# SparkFun_RTK_Facet_-_Cellular.net
KiCad netlist of a schematic drawn in EAGLE
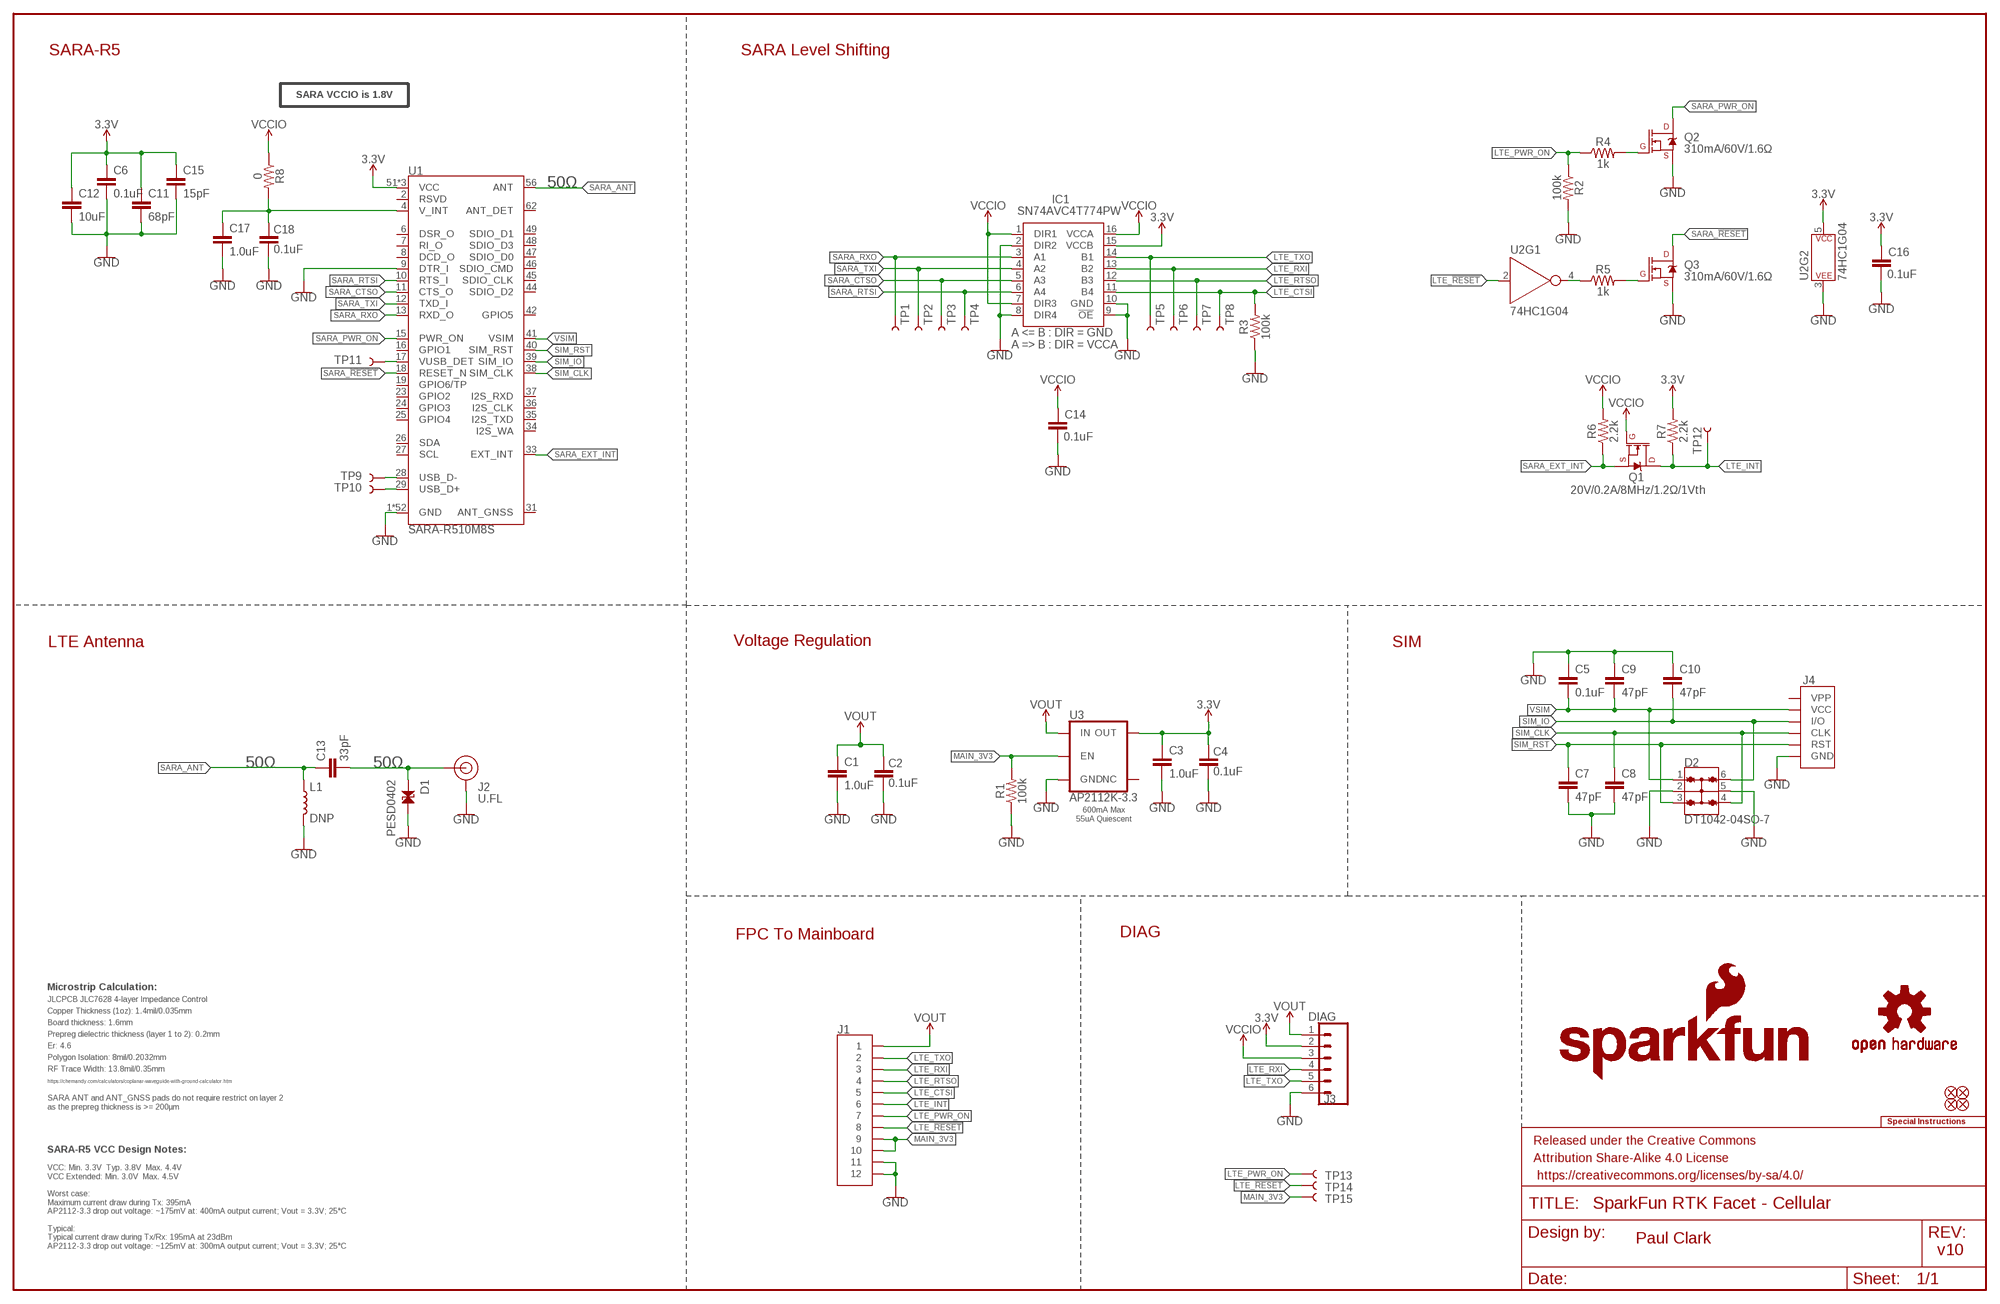
[diagram p0: schematic, sheet 1]

(export (version "E")
  (design (tool "Eeschema 10.0.6"))
  (components
    (comp (ref "C1")
      (value "1.0uF")
      (footprint "eagle-import:0603")
      (libsource (lib "eagle-import") (part "1.0UF-0603-16V-10%-X7R"))
    )
    (comp (ref "C2")
      (value "0.1uF")
      (footprint "eagle-import:0603")
      (libsource (lib "eagle-import") (part "0.1UF-0603-25V-5%"))
    )
    (comp (ref "C3")
      (value "1.0uF")
      (footprint "eagle-import:0603")
      (libsource (lib "eagle-import") (part "1.0UF-0603-16V-10%-X7R"))
    )
    (comp (ref "C4")
      (value "0.1uF")
      (footprint "eagle-import:0603")
      (libsource (lib "eagle-import") (part "0.1UF-0603-25V-5%"))
    )
    (comp (ref "C5")
      (value "0.1uF")
      (footprint "eagle-import:0603")
      (libsource (lib "eagle-import") (part "0.1UF-0603-25V-5%"))
    )
    (comp (ref "C6")
      (value "0.1uF")
      (footprint "eagle-import:0603")
      (libsource (lib "eagle-import") (part "0.1UF-0603-25V-5%"))
    )
    (comp (ref "C7")
      (value "47pF")
      (footprint "eagle-import:0603")
      (libsource (lib "eagle-import") (part "47PF-0603-50V-5%"))
    )
    (comp (ref "C8")
      (value "47pF")
      (footprint "eagle-import:0603")
      (libsource (lib "eagle-import") (part "47PF-0603-50V-5%"))
    )
    (comp (ref "C9")
      (value "47pF")
      (footprint "eagle-import:0603")
      (libsource (lib "eagle-import") (part "47PF-0603-50V-5%"))
    )
    (comp (ref "C10")
      (value "47pF")
      (footprint "eagle-import:0603")
      (libsource (lib "eagle-import") (part "47PF-0603-50V-5%"))
    )
    (comp (ref "C11")
      (value "68pF")
      (footprint "eagle-import:0603")
      (libsource (lib "eagle-import") (part "68PF-0603-50V-5%"))
    )
    (comp (ref "C12")
      (value "10uF")
      (footprint "eagle-import:0603")
      (libsource (lib "eagle-import") (part "10UF-0603-6.3V-20%"))
    )
    (comp (ref "C13")
      (value "33pF")
      (footprint "eagle-import:0402")
      (fields
        (field (name "DIGIKEY_PART") "490-5936-1-ND")
        (field (name "MANUFACTURER") "Murata")
        (field (name "MANU_PART") "GRM1555C1H330JA")
      )
      (libsource (lib "eagle-import") (part "33PF-0402-25V-5%-X7R"))
    )
    (comp (ref "C14")
      (value "0.1uF")
      (footprint "eagle-import:0603")
      (libsource (lib "eagle-import") (part "0.1UF-0603-25V-(+80/-20%)"))
    )
    (comp (ref "C15")
      (value "15pF")
      (footprint "eagle-import:0603")
      (libsource (lib "eagle-import") (part "15PF-0603-50V-5%"))
    )
    (comp (ref "C16")
      (value "0.1uF")
      (footprint "eagle-import:0603")
      (libsource (lib "eagle-import") (part "0.1UF-0603-25V-(+80/-20%)"))
    )
    (comp (ref "C17")
      (value "1.0uF")
      (footprint "eagle-import:0603")
      (libsource (lib "eagle-import") (part "1.0UF-0603-16V-10%-X7R"))
    )
    (comp (ref "C18")
      (value "0.1uF")
      (footprint "eagle-import:0603")
      (libsource (lib "eagle-import") (part "0.1UF-0603-25V-5%"))
    )
    (comp (ref "D1")
      (value "PESD0402")
      (footprint "eagle-import:0402")
      (fields
        (field (name "DIGIKEY_PART") "PESD0402-140CT-ND")
        (field (name "MOUSE_PART") "650-PESD0402-140")
      )
      (libsource (lib "eagle-import") (part "PESD0402"))
    )
    (comp (ref "D2")
      (value "DT1042-04SO-7")
      (footprint "eagle-import:SOT23-6L")
      (libsource (lib "eagle-import") (part "TVS_DIODE_ARRAY_4DT1042-04SO-7"))
    )
    (comp (ref "FID1")
      (value "FIDUCIAL1X2")
      (footprint "eagle-import:FIDUCIAL-1X2")
      (libsource (lib "eagle-import") (part "FIDUCIAL1X2"))
    )
    (comp (ref "FID2")
      (value "FIDUCIAL1X2")
      (footprint "eagle-import:FIDUCIAL-1X2")
      (libsource (lib "eagle-import") (part "FIDUCIAL1X2"))
    )
    (comp (ref "FID3")
      (value "FIDUCIAL1X2")
      (footprint "eagle-import:FIDUCIAL-1X2")
      (libsource (lib "eagle-import") (part "FIDUCIAL1X2"))
    )
    (comp (ref "FID4")
      (value "FIDUCIAL1X2")
      (footprint "eagle-import:FIDUCIAL-1X2")
      (libsource (lib "eagle-import") (part "FIDUCIAL1X2"))
    )
    (comp (ref "FRAME3")
      (value "FRAME-LEDGER")
      (footprint "eagle-import:CREATIVE_COMMONS")
      (libsource (lib "eagle-import") (part "FRAME-LEDGER"))
    )
    (comp (ref "IC1")
      (value "SN74AVC4T774PW")
      (footprint "eagle-import:SOP65P640X120-16N")
      (fields (field (name "MOUSER_PART_NUMBER") "595-SN74AVC4T774PW"))
      (libsource (lib "eagle-import") (part "SN74AVC4T774PW"))
    )
    (comp (ref "J1")
      (value "FPC_12_0.5MM_BACKFLIP")
      (footprint "eagle-import:FPC_12_DOUBLESIDED_BACKFLIP")
      (libsource (lib "eagle-import") (part "FPC_12_0.5MM_BACKFLIP"))
    )
    (comp (ref "J2")
      (value "U.FL")
      (footprint "eagle-import:U.FL")
      (libsource (lib "eagle-import") (part "U.FL2PIN"))
    )
    (comp (ref "J3")
      (value "DIAG")
      (footprint "eagle-import:1X06_NO_SILK")
      (libsource (lib "eagle-import") (part "CONN_06NO_SILK_FEMALE_PTH"))
    )
    (comp (ref "J4")
      (value "SIMHOLDER-PUSHPUSH-REDUCED-PADS")
      (footprint "eagle-import:NANO_SIM_PP_REDUCED_PADS")
      (libsource (lib "eagle-import") (part "SIMHOLDER-PUSHPUSH-REDUCED-PADS"))
    )
    (comp (ref "L1")
      (value "DNP")
      (footprint "eagle-import:0402_COILCRAFT")
      (libsource (lib "eagle-import") (part "INDUCTOR_DNP-0402"))
    )
    (comp (ref "LOGO1")
      (value "SPECIAL_INSTRUCTIONS-ORDERING")
      (footprint "eagle-import:ORDERING_INSTRUCTIONS")
      (libsource (lib "eagle-import") (part "SPECIAL_INSTRUCTIONS-ORDERING"))
    )
    (comp (ref "LOGO2")
      (value "SFE_LOGO_NAME_FLAME.1_INCH")
      (footprint "eagle-import:SFE_LOGO_NAME_FLAME_.1")
      (libsource (lib "eagle-import") (part "SFE_LOGO_NAME_FLAME.1_INCH"))
    )
    (comp (ref "LOGO3")
      (value "OSHW-LOGOMINI")
      (footprint "eagle-import:OSHW-LOGO-MINI")
      (libsource (lib "eagle-import") (part "OSHW-LOGOMINI"))
    )
    (comp (ref "LOGO4")
      (value "OSHW-LOGOMINI")
      (footprint "eagle-import:OSHW-LOGO-MINI")
      (libsource (lib "eagle-import") (part "OSHW-LOGOMINI"))
    )
    (comp (ref "LOGO5")
      (value "SFE_LOGO_NAME_FLAME.1_INCH")
      (footprint "eagle-import:SFE_LOGO_NAME_FLAME_.1")
      (libsource (lib "eagle-import") (part "SFE_LOGO_NAME_FLAME.1_INCH"))
    )
    (comp (ref "Q1")
      (value "20V/0.2A/8MHz/1.2Ω/1Vth")
      (footprint "eagle-import:SOT-416FL")
      (libsource (lib "eagle-import") (part "MOSFET-NCH-RE1C002UNTCL"))
    )
    (comp (ref "Q2")
      (value "310mA/60V/1.6Ω")
      (footprint "eagle-import:SOT323")
      (libsource (lib "eagle-import") (part "MOSFET-NCH-2N7002PW"))
    )
    (comp (ref "Q3")
      (value "310mA/60V/1.6Ω")
      (footprint "eagle-import:SOT323")
      (libsource (lib "eagle-import") (part "MOSFET-NCH-2N7002PW"))
    )
    (comp (ref "R1")
      (value "100k")
      (footprint "eagle-import:0603")
      (libsource (lib "eagle-import") (part "100KOHM-0603-1/10W-1%"))
    )
    (comp (ref "R2")
      (value "100k")
      (footprint "eagle-import:0603")
      (libsource (lib "eagle-import") (part "100KOHM-0603-1/10W-1%"))
    )
    (comp (ref "R3")
      (value "100k")
      (footprint "eagle-import:0603")
      (libsource (lib "eagle-import") (part "100KOHM-0603-1/10W-1%"))
    )
    (comp (ref "R4")
      (value "1k")
      (footprint "eagle-import:0603")
      (libsource (lib "eagle-import") (part "1KOHM-0603-1/10W-1%"))
    )
    (comp (ref "R5")
      (value "1k")
      (footprint "eagle-import:0603")
      (libsource (lib "eagle-import") (part "1KOHM-0603-1/10W-1%"))
    )
    (comp (ref "R6")
      (value "2.2k")
      (footprint "eagle-import:0603")
      (libsource (lib "eagle-import") (part "2.2KOHM-0603-1/10W-1%"))
    )
    (comp (ref "R7")
      (value "2.2k")
      (footprint "eagle-import:0603")
      (libsource (lib "eagle-import") (part "2.2KOHM-0603-1/10W-1%"))
    )
    (comp (ref "R8")
      (value "0")
      (footprint "eagle-import:0603")
      (libsource (lib "eagle-import") (part "0OHM-0603-1/10W"))
    )
    (comp (ref "TP1")
      (value "TEST-POINT3")
      (footprint "eagle-import:PAD.03X.03")
      (libsource (lib "eagle-import") (part "TEST-POINT3"))
    )
    (comp (ref "TP2")
      (value "TEST-POINT3")
      (footprint "eagle-import:PAD.03X.03")
      (libsource (lib "eagle-import") (part "TEST-POINT3"))
    )
    (comp (ref "TP3")
      (value "TEST-POINT3")
      (footprint "eagle-import:PAD.03X.03")
      (libsource (lib "eagle-import") (part "TEST-POINT3"))
    )
    (comp (ref "TP4")
      (value "TEST-POINT3")
      (footprint "eagle-import:PAD.03X.03")
      (libsource (lib "eagle-import") (part "TEST-POINT3"))
    )
    (comp (ref "TP5")
      (value "TEST-POINT3")
      (footprint "eagle-import:PAD.03X.03")
      (libsource (lib "eagle-import") (part "TEST-POINT3"))
    )
    (comp (ref "TP6")
      (value "TEST-POINT3")
      (footprint "eagle-import:PAD.03X.03")
      (libsource (lib "eagle-import") (part "TEST-POINT3"))
    )
    (comp (ref "TP7")
      (value "TEST-POINT3")
      (footprint "eagle-import:PAD.03X.03")
      (libsource (lib "eagle-import") (part "TEST-POINT3"))
    )
    (comp (ref "TP8")
      (value "TEST-POINT3")
      (footprint "eagle-import:PAD.03X.03")
      (libsource (lib "eagle-import") (part "TEST-POINT3"))
    )
    (comp (ref "TP9")
      (value "TEST-POINT3")
      (footprint "eagle-import:PAD.03X.03")
      (libsource (lib "eagle-import") (part "TEST-POINT3"))
    )
    (comp (ref "TP10")
      (value "TEST-POINT3")
      (footprint "eagle-import:PAD.03X.03")
      (libsource (lib "eagle-import") (part "TEST-POINT3"))
    )
    (comp (ref "TP11")
      (value "TEST-POINT3")
      (footprint "eagle-import:PAD.03X.03")
      (libsource (lib "eagle-import") (part "TEST-POINT3"))
    )
    (comp (ref "TP12")
      (value "TEST-POINT3")
      (footprint "eagle-import:PAD.03X.03")
      (libsource (lib "eagle-import") (part "TEST-POINT3"))
    )
    (comp (ref "TP13")
      (value "TEST-POINT3")
      (footprint "eagle-import:PAD.03X.03")
      (libsource (lib "eagle-import") (part "TEST-POINT3"))
    )
    (comp (ref "TP14")
      (value "TEST-POINT3")
      (footprint "eagle-import:PAD.03X.03")
      (libsource (lib "eagle-import") (part "TEST-POINT3"))
    )
    (comp (ref "TP15")
      (value "TEST-POINT3")
      (footprint "eagle-import:PAD.03X.03")
      (libsource (lib "eagle-import") (part "TEST-POINT3"))
    )
    (comp (ref "U1")
      (value "SARA-R510M8S")
      (footprint "eagle-import:SARA-LGA")
      (libsource (lib "eagle-import") (part "SARA-R510M8S"))
    )
    (comp (ref "U2")
      (value "74HC1G04")
      (footprint "eagle-import:SOT353")
      (libsource (lib "eagle-import") (part "741G04HC"))
    )
    (comp (ref "U3")
      (value "AP2112K-3.3")
      (footprint "eagle-import:SOT23-5")
      (libsource (lib "eagle-import") (part "V_REG_AP2112K-3.3V"))
    )
  )
  (nets
    (net (code "1") (name "/LTE_~{RESET}") (class "Default")
      (node (ref "J1") (pin "8") (pinfunction "8_8") (pintype "bidirectional"))
      (node (ref "TP14") (pin "1") (pinfunction "1_1") (pintype "bidirectional"))
      (node (ref "U2") (pin "2") (pinfunction "A_2") (pintype "bidirectional"))
    )
    (net (code "2") (name "/SARA_~{RESET}") (class "Default")
      (node (ref "Q3") (pin "3") (pinfunction "D_3") (pintype "bidirectional"))
      (node (ref "U1") (pin "18") (pinfunction "RESET_N_18") (pintype "input"))
    )
    (net (code "3") (name "3.3V") (class "Default")
      (node (ref "C11") (pin "1") (pinfunction "1_1") (pintype "passive"))
      (node (ref "C12") (pin "1") (pinfunction "1_1") (pintype "passive"))
      (node (ref "C15") (pin "1") (pinfunction "1_1") (pintype "passive"))
      (node (ref "C16") (pin "1") (pinfunction "1_1") (pintype "passive"))
      (node (ref "C3") (pin "1") (pinfunction "1_1") (pintype "passive"))
      (node (ref "C4") (pin "2") (pinfunction "2_2") (pintype "passive"))
      (node (ref "C6") (pin "1") (pinfunction "1_1") (pintype "passive"))
      (node (ref "IC1") (pin "15") (pinfunction "VCCB_15") (pintype "power_in"))
      (node (ref "J3") (pin "2") (pinfunction "2_2") (pintype "passive"))
      (node (ref "R7") (pin "2") (pinfunction "2_2") (pintype "passive"))
      (node (ref "U1") (pin "51") (pinfunction "VCC_51") (pintype "power_in"))
      (node (ref "U1") (pin "52") (pinfunction "VCC_52") (pintype "power_in"))
      (node (ref "U1") (pin "53") (pinfunction "VCC_53") (pintype "power_in"))
      (node (ref "U2") (pin "5") (pinfunction "P$V+_5") (pintype "bidirectional"))
      (node (ref "U3") (pin "5") (pinfunction "OUT_5") (pintype "passive"))
    )
    (net (code "4") (name "GND") (class "Default")
      (node (ref "C1") (pin "2") (pinfunction "2_2") (pintype "passive"))
      (node (ref "C10") (pin "1") (pinfunction "1_1") (pintype "passive"))
      (node (ref "C11") (pin "2") (pinfunction "2_2") (pintype "passive"))
      (node (ref "C12") (pin "2") (pinfunction "2_2") (pintype "passive"))
      (node (ref "C14") (pin "2") (pinfunction "2_2") (pintype "passive"))
      (node (ref "C15") (pin "2") (pinfunction "2_2") (pintype "passive"))
      (node (ref "C16") (pin "2") (pinfunction "2_2") (pintype "passive"))
      (node (ref "C17") (pin "2") (pinfunction "2_2") (pintype "passive"))
      (node (ref "C18") (pin "1") (pinfunction "1_1") (pintype "passive"))
      (node (ref "C2") (pin "1") (pinfunction "1_1") (pintype "passive"))
      (node (ref "C3") (pin "2") (pinfunction "2_2") (pintype "passive"))
      (node (ref "C4") (pin "1") (pinfunction "1_1") (pintype "passive"))
      (node (ref "C5") (pin "1") (pinfunction "1_1") (pintype "passive"))
      (node (ref "C6") (pin "2") (pinfunction "2_2") (pintype "passive"))
      (node (ref "C7") (pin "2") (pinfunction "2_2") (pintype "passive"))
      (node (ref "C8") (pin "2") (pinfunction "2_2") (pintype "passive"))
      (node (ref "C9") (pin "1") (pinfunction "1_1") (pintype "passive"))
      (node (ref "D1") (pin "2") (pinfunction "2_2") (pintype "bidirectional"))
      (node (ref "D2") (pin "2") (pinfunction "2_2") (pintype "bidirectional"))
      (node (ref "D2") (pin "5") (pinfunction "5_5") (pintype "bidirectional"))
      (node (ref "IC1") (pin "10") (pinfunction "GND_10") (pintype "power_in"))
      (node (ref "IC1") (pin "2") (pinfunction "DIR2_2") (pintype "input"))
      (node (ref "IC1") (pin "8") (pinfunction "DIR4_8") (pintype "input"))
      (node (ref "IC1") (pin "9") (pinfunction "~{OE}_9") (pintype "input"))
      (node (ref "J1") (pin "11") (pinfunction "11_11") (pintype "bidirectional"))
      (node (ref "J1") (pin "12") (pinfunction "12_12") (pintype "bidirectional"))
      (node (ref "J2") (pin "1") (pinfunction "GND_1") (pintype "bidirectional"))
      (node (ref "J2") (pin "2") (pinfunction "GND_2") (pintype "bidirectional"))
      (node (ref "J3") (pin "6") (pinfunction "6_6") (pintype "passive"))
      (node (ref "J4") (pin "C5") (pinfunction "GND_C5") (pintype "power_in"))
      (node (ref "L1") (pin "P$2") (pinfunction "2_P$2") (pintype "passive"))
      (node (ref "Q2") (pin "2") (pinfunction "S_2") (pintype "bidirectional"))
      (node (ref "Q3") (pin "2") (pinfunction "S_2") (pintype "bidirectional"))
      (node (ref "R1") (pin "1") (pinfunction "1_1") (pintype "passive"))
      (node (ref "R2") (pin "2") (pinfunction "2_2") (pintype "passive"))
      (node (ref "R3") (pin "1") (pinfunction "1_1") (pintype "passive"))
      (node (ref "U1") (pin "1") (pinfunction "GND_1") (pintype "power_in"))
      (node (ref "U1") (pin "14") (pinfunction "GND_14") (pintype "power_in"))
      (node (ref "U1") (pin "20") (pinfunction "GND_20") (pintype "power_in"))
      (node (ref "U1") (pin "21") (pinfunction "GND_21") (pintype "power_in"))
      (node (ref "U1") (pin "22") (pinfunction "GND_22") (pintype "power_in"))
      (node (ref "U1") (pin "3") (pinfunction "GND_3") (pintype "power_in"))
      (node (ref "U1") (pin "30") (pinfunction "GND_30") (pintype "power_in"))
      (node (ref "U1") (pin "32") (pinfunction "GND_32") (pintype "power_in"))
      (node (ref "U1") (pin "43") (pinfunction "GND_43") (pintype "power_in"))
      (node (ref "U1") (pin "5") (pinfunction "GND_5") (pintype "power_in"))
      (node (ref "U1") (pin "50") (pinfunction "GND_50") (pintype "power_in"))
      (node (ref "U1") (pin "54") (pinfunction "GND_54") (pintype "power_in"))
      (node (ref "U1") (pin "55") (pinfunction "GND_55") (pintype "power_in"))
      (node (ref "U1") (pin "57") (pinfunction "GND_57") (pintype "power_in"))
      (node (ref "U1") (pin "58") (pinfunction "GND_58") (pintype "power_in"))
      (node (ref "U1") (pin "59") (pinfunction "GND_59") (pintype "power_in"))
      (node (ref "U1") (pin "60") (pinfunction "GND_60") (pintype "power_in"))
      (node (ref "U1") (pin "61") (pinfunction "GND_61") (pintype "power_in"))
      (node (ref "U1") (pin "63") (pinfunction "GND_63") (pintype "power_in"))
      (node (ref "U1") (pin "64") (pinfunction "GND_64") (pintype "power_in"))
      (node (ref "U1") (pin "65") (pinfunction "GND_65") (pintype "power_in"))
      (node (ref "U1") (pin "66") (pinfunction "GND_66") (pintype "power_in"))
      (node (ref "U1") (pin "67") (pinfunction "GND_67") (pintype "power_in"))
      (node (ref "U1") (pin "68") (pinfunction "GND_68") (pintype "power_in"))
      (node (ref "U1") (pin "69") (pinfunction "GND_69") (pintype "power_in"))
      (node (ref "U1") (pin "70") (pinfunction "GND_70") (pintype "power_in"))
      (node (ref "U1") (pin "71") (pinfunction "GND_71") (pintype "power_in"))
      (node (ref "U1") (pin "72") (pinfunction "GND_72") (pintype "power_in"))
      (node (ref "U1") (pin "73") (pinfunction "GND_73") (pintype "power_in"))
      (node (ref "U1") (pin "74") (pinfunction "GND_74") (pintype "power_in"))
      (node (ref "U1") (pin "75") (pinfunction "GND_75") (pintype "power_in"))
      (node (ref "U1") (pin "76") (pinfunction "GND_76") (pintype "power_in"))
      (node (ref "U1") (pin "77") (pinfunction "GND_77") (pintype "power_in"))
      (node (ref "U1") (pin "78") (pinfunction "GND_78") (pintype "power_in"))
      (node (ref "U1") (pin "79") (pinfunction "GND_79") (pintype "power_in"))
      (node (ref "U1") (pin "80") (pinfunction "GND_80") (pintype "power_in"))
      (node (ref "U1") (pin "81") (pinfunction "GND_81") (pintype "power_in"))
      (node (ref "U1") (pin "82") (pinfunction "GND_82") (pintype "power_in"))
      (node (ref "U1") (pin "83") (pinfunction "GND_83") (pintype "power_in"))
      (node (ref "U1") (pin "84") (pinfunction "GND_84") (pintype "power_in"))
      (node (ref "U1") (pin "85") (pinfunction "GND_85") (pintype "power_in"))
      (node (ref "U1") (pin "86") (pinfunction "GND_86") (pintype "power_in"))
      (node (ref "U1") (pin "87") (pinfunction "GND_87") (pintype "power_in"))
      (node (ref "U1") (pin "88") (pinfunction "GND_88") (pintype "power_in"))
      (node (ref "U1") (pin "89") (pinfunction "GND_89") (pintype "power_in"))
      (node (ref "U1") (pin "9") (pinfunction "DTR_I_9") (pintype "input"))
      (node (ref "U1") (pin "90") (pinfunction "GND_90") (pintype "power_in"))
      (node (ref "U1") (pin "91") (pinfunction "GND_91") (pintype "power_in"))
      (node (ref "U1") (pin "92") (pinfunction "GND_92") (pintype "power_in"))
      (node (ref "U1") (pin "93") (pinfunction "GND_93") (pintype "power_in"))
      (node (ref "U1") (pin "94") (pinfunction "GND_94") (pintype "power_in"))
      (node (ref "U1") (pin "95") (pinfunction "GND_95") (pintype "power_in"))
      (node (ref "U1") (pin "96") (pinfunction "GND_96") (pintype "power_in"))
      (node (ref "U2") (pin "3") (pinfunction "P$V-_3") (pintype "bidirectional"))
      (node (ref "U3") (pin "2") (pinfunction "GND_2") (pintype "input"))
    )
    (net (code "5") (name "LTE_CTSI") (class "Default")
      (node (ref "IC1") (pin "11") (pinfunction "B4_11") (pintype "bidirectional"))
      (node (ref "J1") (pin "5") (pinfunction "5_5") (pintype "bidirectional"))
      (node (ref "R3") (pin "2") (pinfunction "2_2") (pintype "passive"))
      (node (ref "TP8") (pin "1") (pinfunction "1_1") (pintype "bidirectional"))
    )
    (net (code "6") (name "LTE_INT") (class "Default")
      (node (ref "J1") (pin "6") (pinfunction "6_6") (pintype "bidirectional"))
      (node (ref "Q1") (pin "3") (pinfunction "D_3") (pintype "bidirectional"))
      (node (ref "R7") (pin "1") (pinfunction "1_1") (pintype "passive"))
      (node (ref "TP12") (pin "1") (pinfunction "1_1") (pintype "bidirectional"))
    )
    (net (code "7") (name "LTE_PWR_ON") (class "Default")
      (node (ref "J1") (pin "7") (pinfunction "7_7") (pintype "bidirectional"))
      (node (ref "R2") (pin "1") (pinfunction "1_1") (pintype "passive"))
      (node (ref "R4") (pin "1") (pinfunction "1_1") (pintype "passive"))
      (node (ref "TP13") (pin "1") (pinfunction "1_1") (pintype "bidirectional"))
    )
    (net (code "8") (name "LTE_RTSO") (class "Default")
      (node (ref "IC1") (pin "12") (pinfunction "B3_12") (pintype "bidirectional"))
      (node (ref "J1") (pin "4") (pinfunction "4_4") (pintype "bidirectional"))
      (node (ref "TP7") (pin "1") (pinfunction "1_1") (pintype "bidirectional"))
    )
    (net (code "9") (name "LTE_RXI") (class "Default")
      (node (ref "IC1") (pin "13") (pinfunction "B2_13") (pintype "bidirectional"))
      (node (ref "J1") (pin "3") (pinfunction "3_3") (pintype "bidirectional"))
      (node (ref "J3") (pin "4") (pinfunction "4_4") (pintype "passive"))
      (node (ref "TP6") (pin "1") (pinfunction "1_1") (pintype "bidirectional"))
    )
    (net (code "10") (name "LTE_TXO") (class "Default")
      (node (ref "IC1") (pin "14") (pinfunction "B1_14") (pintype "bidirectional"))
      (node (ref "J1") (pin "2") (pinfunction "2_2") (pintype "bidirectional"))
      (node (ref "J3") (pin "5") (pinfunction "5_5") (pintype "passive"))
      (node (ref "TP5") (pin "1") (pinfunction "1_1") (pintype "bidirectional"))
    )
    (net (code "11") (name "MAIN_3V3") (class "Default")
      (node (ref "J1") (pin "10") (pinfunction "10_10") (pintype "bidirectional"))
      (node (ref "J1") (pin "9") (pinfunction "9_9") (pintype "bidirectional"))
      (node (ref "R1") (pin "2") (pinfunction "2_2") (pintype "passive"))
      (node (ref "TP15") (pin "1") (pinfunction "1_1") (pintype "bidirectional"))
      (node (ref "U3") (pin "3") (pinfunction "EN_3") (pintype "input"))
    )
    (net (code "12") (name "Net-(J2-SIGNAL)") (class "Default")
      (node (ref "C13") (pin "2") (pinfunction "2_2") (pintype "passive"))
      (node (ref "D1") (pin "1") (pinfunction "1_1") (pintype "bidirectional"))
      (node (ref "J2") (pin "FEED") (pinfunction "SIGNAL_FEED") (pintype "bidirectional"))
    )
    (net (code "13") (name "Net-(Q2-G)") (class "Default")
      (node (ref "Q2") (pin "1") (pinfunction "G_1") (pintype "bidirectional"))
      (node (ref "R4") (pin "2") (pinfunction "2_2") (pintype "passive"))
    )
    (net (code "14") (name "Net-(Q3-G)") (class "Default")
      (node (ref "Q3") (pin "1") (pinfunction "G_1") (pintype "bidirectional"))
      (node (ref "R5") (pin "2") (pinfunction "2_2") (pintype "passive"))
    )
    (net (code "15") (name "Net-(U1-USB_D+)") (class "Default")
      (node (ref "TP10") (pin "1") (pinfunction "1_1") (pintype "bidirectional"))
      (node (ref "U1") (pin "29") (pinfunction "USB_D+_29") (pintype "bidirectional"))
    )
    (net (code "16") (name "Net-(U1-USB_D-)") (class "Default")
      (node (ref "TP9") (pin "1") (pinfunction "1_1") (pintype "bidirectional"))
      (node (ref "U1") (pin "28") (pinfunction "USB_D-_28") (pintype "bidirectional"))
    )
    (net (code "17") (name "Net-(U1-VUSB_DET)") (class "Default")
      (node (ref "TP11") (pin "1") (pinfunction "1_1") (pintype "bidirectional"))
      (node (ref "U1") (pin "17") (pinfunction "VUSB_DET_17") (pintype "input"))
    )
    (net (code "18") (name "Net-(U1-V_INT)") (class "Default")
      (node (ref "C17") (pin "1") (pinfunction "1_1") (pintype "passive"))
      (node (ref "C18") (pin "2") (pinfunction "2_2") (pintype "passive"))
      (node (ref "R8") (pin "2") (pinfunction "2_2") (pintype "passive"))
      (node (ref "U1") (pin "4") (pinfunction "V_INT_4") (pintype "output"))
    )
    (net (code "19") (name "Net-(U2A-Y)") (class "Default")
      (node (ref "R5") (pin "1") (pinfunction "1_1") (pintype "passive"))
      (node (ref "U2") (pin "4") (pinfunction "Y_4") (pintype "bidirectional"))
    )
    (net (code "20") (name "SARA_ANT") (class "Default")
      (node (ref "C13") (pin "1") (pinfunction "1_1") (pintype "passive"))
      (node (ref "L1") (pin "P$1") (pinfunction "1_P$1") (pintype "passive"))
      (node (ref "U1") (pin "56") (pinfunction "ANT_56") (pintype "bidirectional"))
    )
    (net (code "21") (name "SARA_CTSO") (class "Default")
      (node (ref "IC1") (pin "5") (pinfunction "A3_5") (pintype "bidirectional"))
      (node (ref "TP3") (pin "1") (pinfunction "1_1") (pintype "bidirectional"))
      (node (ref "U1") (pin "11") (pinfunction "CTS_O_11") (pintype "output"))
    )
    (net (code "22") (name "SARA_EXT_INT") (class "Default")
      (node (ref "Q1") (pin "2") (pinfunction "S_2") (pintype "bidirectional"))
      (node (ref "R6") (pin "1") (pinfunction "1_1") (pintype "passive"))
      (node (ref "U1") (pin "33") (pinfunction "EXT_INT_33") (pintype "input"))
    )
    (net (code "23") (name "SARA_PWR_ON") (class "Default")
      (node (ref "Q2") (pin "3") (pinfunction "D_3") (pintype "bidirectional"))
      (node (ref "U1") (pin "15") (pinfunction "PWR_ON_15") (pintype "input"))
    )
    (net (code "24") (name "SARA_RTSI") (class "Default")
      (node (ref "IC1") (pin "6") (pinfunction "A4_6") (pintype "bidirectional"))
      (node (ref "TP4") (pin "1") (pinfunction "1_1") (pintype "bidirectional"))
      (node (ref "U1") (pin "10") (pinfunction "RTS_I_10") (pintype "input"))
    )
    (net (code "25") (name "SARA_RXO") (class "Default")
      (node (ref "IC1") (pin "3") (pinfunction "A1_3") (pintype "bidirectional"))
      (node (ref "TP1") (pin "1") (pinfunction "1_1") (pintype "bidirectional"))
      (node (ref "U1") (pin "13") (pinfunction "RXD_O_13") (pintype "output"))
    )
    (net (code "26") (name "SARA_TXI") (class "Default")
      (node (ref "IC1") (pin "4") (pinfunction "A2_4") (pintype "bidirectional"))
      (node (ref "TP2") (pin "1") (pinfunction "1_1") (pintype "bidirectional"))
      (node (ref "U1") (pin "12") (pinfunction "TXD_I_12") (pintype "input"))
    )
    (net (code "27") (name "SIM_CLK") (class "Default")
      (node (ref "C8") (pin "1") (pinfunction "1_1") (pintype "passive"))
      (node (ref "D2") (pin "4") (pinfunction "4_4") (pintype "bidirectional"))
      (node (ref "J4") (pin "C3") (pinfunction "CLK_C3") (pintype "input"))
      (node (ref "U1") (pin "38") (pinfunction "SIM_CLK_38") (pintype "output"))
    )
    (net (code "28") (name "SIM_IO") (class "Default")
      (node (ref "C10") (pin "2") (pinfunction "2_2") (pintype "passive"))
      (node (ref "D2") (pin "6") (pinfunction "6_6") (pintype "bidirectional"))
      (node (ref "J4") (pin "C7") (pinfunction "I/O_C7") (pintype "bidirectional"))
      (node (ref "U1") (pin "39") (pinfunction "SIM_IO_39") (pintype "bidirectional"))
    )
    (net (code "29") (name "SIM_RST") (class "Default")
      (node (ref "C7") (pin "1") (pinfunction "1_1") (pintype "passive"))
      (node (ref "D2") (pin "3") (pinfunction "3_3") (pintype "bidirectional"))
      (node (ref "J4") (pin "C2") (pinfunction "RST_C2") (pintype "input"))
      (node (ref "U1") (pin "40") (pinfunction "SIM_RST_40") (pintype "output"))
    )
    (net (code "30") (name "VCCIO") (class "Default")
      (node (ref "C14") (pin "1") (pinfunction "1_1") (pintype "passive"))
      (node (ref "IC1") (pin "1") (pinfunction "DIR1_1") (pintype "input"))
      (node (ref "IC1") (pin "16") (pinfunction "VCCA_16") (pintype "power_in"))
      (node (ref "IC1") (pin "7") (pinfunction "DIR3_7") (pintype "input"))
      (node (ref "J3") (pin "3") (pinfunction "3_3") (pintype "passive"))
      (node (ref "Q1") (pin "1") (pinfunction "G_1") (pintype "bidirectional"))
      (node (ref "R6") (pin "2") (pinfunction "2_2") (pintype "passive"))
      (node (ref "R8") (pin "1") (pinfunction "1_1") (pintype "passive"))
    )
    (net (code "31") (name "VOUT") (class "Default")
      (node (ref "C1") (pin "1") (pinfunction "1_1") (pintype "passive"))
      (node (ref "C2") (pin "2") (pinfunction "2_2") (pintype "passive"))
      (node (ref "J1") (pin "1") (pinfunction "1_1") (pintype "bidirectional"))
      (node (ref "J3") (pin "1") (pinfunction "1_1") (pintype "passive"))
      (node (ref "U3") (pin "1") (pinfunction "IN_1") (pintype "input"))
    )
    (net (code "32") (name "VSIM") (class "Default")
      (node (ref "C5") (pin "2") (pinfunction "2_2") (pintype "passive"))
      (node (ref "C9") (pin "2") (pinfunction "2_2") (pintype "passive"))
      (node (ref "D2") (pin "1") (pinfunction "1_1") (pintype "bidirectional"))
      (node (ref "J4") (pin "C1") (pinfunction "VCC_C1") (pintype "power_in"))
      (node (ref "U1") (pin "41") (pinfunction "VSIM_41") (pintype "output"))
    )
    (net (code "33") (name "unconnected-(J4-VPP-PadC6)") (class "Default")
      (node (ref "J4") (pin "C6") (pinfunction "VPP_C6") (pintype "input"))
    )
    (net (code "34") (name "unconnected-(U1-ANT_DET-Pad62)") (class "Default")
      (node (ref "U1") (pin "62") (pinfunction "ANT_DET_62") (pintype "input"))
    )
    (net (code "35") (name "unconnected-(U1-ANT_GNSS-Pad31)") (class "Default")
      (node (ref "U1") (pin "31") (pinfunction "ANT_GNSS_31") (pintype "input"))
    )
    (net (code "36") (name "unconnected-(U1-DCD_O-Pad8)") (class "Default")
      (node (ref "U1") (pin "8") (pinfunction "DCD_O_8") (pintype "output"))
    )
    (net (code "37") (name "unconnected-(U1-DSR_O-Pad6)") (class "Default")
      (node (ref "U1") (pin "6") (pinfunction "DSR_O_6") (pintype "output"))
    )
    (net (code "38") (name "unconnected-(U1-GPIO1-Pad16)") (class "Default")
      (node (ref "U1") (pin "16") (pinfunction "GPIO1_16") (pintype "bidirectional"))
    )
    (net (code "39") (name "unconnected-(U1-GPIO2-Pad23)") (class "Default")
      (node (ref "U1") (pin "23") (pinfunction "GPIO2_23") (pintype "bidirectional"))
    )
    (net (code "40") (name "unconnected-(U1-GPIO3-Pad24)") (class "Default")
      (node (ref "U1") (pin "24") (pinfunction "GPIO3_24") (pintype "bidirectional"))
    )
    (net (code "41") (name "unconnected-(U1-GPIO4-Pad25)") (class "Default")
      (node (ref "U1") (pin "25") (pinfunction "GPIO4_25") (pintype "bidirectional"))
    )
    (net (code "42") (name "unconnected-(U1-GPIO5-Pad42)") (class "Default")
      (node (ref "U1") (pin "42") (pinfunction "GPIO5_42") (pintype "bidirectional"))
    )
    (net (code "43") (name "unconnected-(U1-GPIO6{slash}TP-Pad19)") (class "Default")
      (node (ref "U1") (pin "19") (pinfunction "GPIO6/TP_19") (pintype "bidirectional"))
    )
    (net (code "44") (name "unconnected-(U1-I2S_CLK-Pad36)") (class "Default")
      (node (ref "U1") (pin "36") (pinfunction "I2S_CLK_36") (pintype "output"))
    )
    (net (code "45") (name "unconnected-(U1-I2S_RXD-Pad37)") (class "Default")
      (node (ref "U1") (pin "37") (pinfunction "I2S_RXD_37") (pintype "input"))
    )
    (net (code "46") (name "unconnected-(U1-I2S_TXD-Pad35)") (class "Default")
      (node (ref "U1") (pin "35") (pinfunction "I2S_TXD_35") (pintype "output"))
    )
    (net (code "47") (name "unconnected-(U1-I2S_WA-Pad34)") (class "Default")
      (node (ref "U1") (pin "34") (pinfunction "I2S_WA_34") (pintype "output"))
    )
    (net (code "48") (name "unconnected-(U1-RI_O-Pad7)") (class "Default")
      (node (ref "U1") (pin "7") (pinfunction "RI_O_7") (pintype "output"))
    )
    (net (code "49") (name "unconnected-(U1-RSVD-Pad2)") (class "Default")
      (node (ref "U1") (pin "2") (pinfunction "RSVD_2") (pintype "no_connect"))
    )
    (net (code "50") (name "unconnected-(U1-SCL-Pad27)") (class "Default")
      (node (ref "U1") (pin "27") (pinfunction "SCL_27") (pintype "bidirectional"))
    )
    (net (code "51") (name "unconnected-(U1-SDA-Pad26)") (class "Default")
      (node (ref "U1") (pin "26") (pinfunction "SDA_26") (pintype "bidirectional"))
    )
    (net (code "52") (name "unconnected-(U1-SDIO_CLK-Pad45)") (class "Default")
      (node (ref "U1") (pin "45") (pinfunction "SDIO_CLK_45") (pintype "output"))
    )
    (net (code "53") (name "unconnected-(U1-SDIO_CMD-Pad46)") (class "Default")
      (node (ref "U1") (pin "46") (pinfunction "SDIO_CMD_46") (pintype "bidirectional"))
    )
    (net (code "54") (name "unconnected-(U1-SDIO_D0-Pad47)") (class "Default")
      (node (ref "U1") (pin "47") (pinfunction "SDIO_D0_47") (pintype "bidirectional"))
    )
    (net (code "55") (name "unconnected-(U1-SDIO_D1-Pad49)") (class "Default")
      (node (ref "U1") (pin "49") (pinfunction "SDIO_D1_49") (pintype "bidirectional"))
    )
    (net (code "56") (name "unconnected-(U1-SDIO_D2-Pad44)") (class "Default")
      (node (ref "U1") (pin "44") (pinfunction "SDIO_D2_44") (pintype "bidirectional"))
    )
    (net (code "57") (name "unconnected-(U1-SDIO_D3-Pad48)") (class "Default")
      (node (ref "U1") (pin "48") (pinfunction "SDIO_D3_48") (pintype "bidirectional"))
    )
    (net (code "58") (name "unconnected-(U3-NC-Pad4)") (class "Default")
      (node (ref "U3") (pin "4") (pinfunction "NC_4") (pintype "no_connect"))
    )
  )
)
